# image_reject.net
KiCad netlist of a schematic drawn in Altium Designer
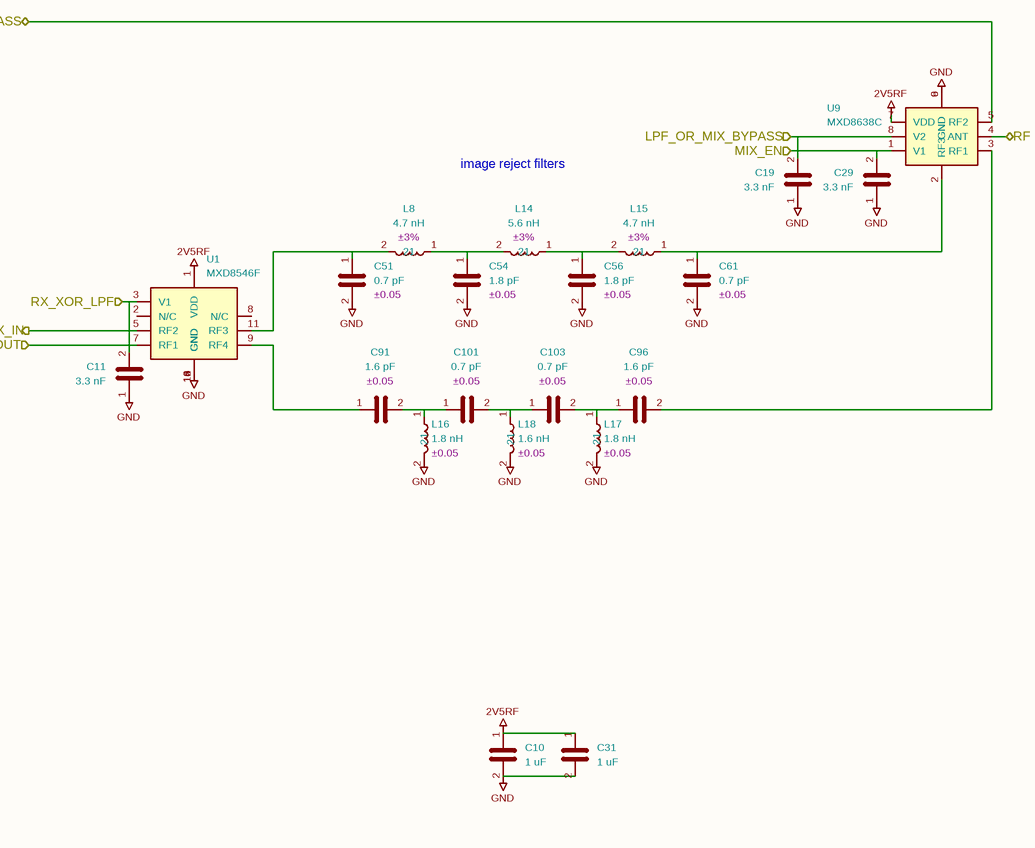
[diagram p0: image_reject.SchDoc]

(export (version "E")
  (design (tool "Eeschema 10.0.6"))
  (components
    (comp (ref "C10")
      (value "1 uF")
      (footprint "C_0201_0603Metric")
      (description "CAP CER 1UF 10V X5R 0201")
      (fields (field (name "MANUFACTURER") "Murata") (field (name "PART NUMBER") "GRM033R61A105ME44D"))
      (libsource (lib "Device") (part "C"))
    )
    (comp (ref "C11")
      (value "3.3 nF")
      (footprint "C_0201_0603Metric")
      (description "CAP CER 3300PF 10V X7R 0201")
      (fields (field (name "MANUFACTURER") "Murata") (field (name "PART NUMBER") "GRM033R71A332KA01D"))
      (libsource (lib "Device") (part "C"))
    )
    (comp (ref "C19")
      (value "3.3 nF")
      (footprint "C_0201_0603Metric")
      (description "CAP CER 3300PF 10V X7R 0201")
      (fields (field (name "MANUFACTURER") "Murata") (field (name "PART NUMBER") "GRM033R71A332KA01D"))
      (libsource (lib "Device") (part "C"))
    )
    (comp (ref "C29")
      (value "3.3 nF")
      (footprint "C_0201_0603Metric")
      (description "CAP CER 3300PF 10V X7R 0201")
      (fields (field (name "MANUFACTURER") "Murata") (field (name "PART NUMBER") "GRM033R71A332KA01D"))
      (libsource (lib "Device") (part "C"))
    )
    (comp (ref "C31")
      (value "1 uF")
      (footprint "C_0201_0603Metric")
      (description "CAP CER 1UF 10V X5R 0201")
      (fields (field (name "MANUFACTURER") "Murata") (field (name "PART NUMBER") "GRM033R61A105ME44D"))
      (libsource (lib "Device") (part "C"))
    )
    (comp (ref "C51")
      (value "0.7 pF")
      (footprint "C_0201_0603Metric")
      (description "CAP CER 0.7PF 25V C0G/NP0 0201")
      (fields
        (field (name "MANUFACTURER") "Murata")
        (field (name "PART NUMBER") "GRM0335C1ER70WA01D")
        (field (name "TOLERANCE") "±0.05")
      )
      (libsource (lib "Device") (part "C"))
    )
    (comp (ref "C54")
      (value "1.8 pF")
      (footprint "C_0201_0603Metric")
      (description "CAP CER 1.8PF 25V C0G/NP0 0201")
      (fields
        (field (name "MANUFACTURER") "Murata")
        (field (name "PART NUMBER") "GRM0335C1E1R8WA01D")
        (field (name "TOLERANCE") "±0.05")
      )
      (libsource (lib "Device") (part "C"))
    )
    (comp (ref "C56")
      (value "1.8 pF")
      (footprint "C_0201_0603Metric")
      (description "CAP CER 1.8PF 25V C0G/NP0 0201")
      (fields
        (field (name "MANUFACTURER") "Murata")
        (field (name "PART NUMBER") "GRM0335C1E1R8WA01D")
        (field (name "TOLERANCE") "±0.05")
      )
      (libsource (lib "Device") (part "C"))
    )
    (comp (ref "C61")
      (value "0.7 pF")
      (footprint "C_0201_0603Metric")
      (description "CAP CER 0.7PF 25V C0G/NP0 0201")
      (fields
        (field (name "MANUFACTURER") "Murata")
        (field (name "PART NUMBER") "GRM0335C1ER70WA01D")
        (field (name "TOLERANCE") "±0.05")
      )
      (libsource (lib "Device") (part "C"))
    )
    (comp (ref "C91")
      (value "1.6 pF")
      (footprint "C_0201_0603Metric")
      (description "CAP CER 1.6PF 25V C0G/NP0 0201")
      (fields
        (field (name "MANUFACTURER") "Murata")
        (field (name "PART NUMBER") "GRM0335C1E1R6WA01D")
        (field (name "TOLERANCE") "±0.05")
      )
      (libsource (lib "Device") (part "C"))
    )
    (comp (ref "C96")
      (value "1.6 pF")
      (footprint "C_0201_0603Metric")
      (description "CAP CER 1.6PF 25V C0G/NP0 0201")
      (fields
        (field (name "MANUFACTURER") "Murata")
        (field (name "PART NUMBER") "GRM0335C1E1R6WA01D")
        (field (name "TOLERANCE") "±0.05")
      )
      (libsource (lib "Device") (part "C"))
    )
    (comp (ref "C101")
      (value "0.7 pF")
      (footprint "C_0201_0603Metric")
      (description "CAP CER 0.7PF 25V C0G/NP0 0201")
      (fields
        (field (name "MANUFACTURER") "Murata")
        (field (name "PART NUMBER") "GRM0335C1ER70WA01D")
        (field (name "TOLERANCE") "±0.05")
      )
      (libsource (lib "Device") (part "C"))
    )
    (comp (ref "C103")
      (value "0.7 pF")
      (footprint "C_0201_0603Metric")
      (description "CAP CER 0.7PF 25V C0G/NP0 0201")
      (fields
        (field (name "MANUFACTURER") "Murata")
        (field (name "PART NUMBER") "GRM0335C1ER70WA01D")
        (field (name "TOLERANCE") "±0.05")
      )
      (libsource (lib "Device") (part "C"))
    )
    (comp (ref "L8")
      (value "4.7 nH")
      (footprint "L_0201_0603Metric")
      (description "FIXED IND 4.7NH 350MA 400MOHM 0201")
      (fields
        (field (name "MANUFACTURER") "Murata")
        (field (name "PART NUMBER") "LQP03TN4N7H02D")
        (field (name "TOLERANCE") "±3%")
      )
      (libsource (lib "Device") (part "L"))
    )
    (comp (ref "L14")
      (value "5.6 nH")
      (footprint "L_0201_0603Metric")
      (description "FIXED IND 5.6NH 350MA 400MOHM 0201")
      (fields
        (field (name "MANUFACTURER") "Murata")
        (field (name "PART NUMBER") "LQP03TN5N6H02D")
        (field (name "TOLERANCE") "±3%")
      )
      (libsource (lib "Device") (part "L"))
    )
    (comp (ref "L15")
      (value "4.7 nH")
      (footprint "L_0201_0603Metric")
      (description "FIXED IND 4.7NH 350MA 400MOHM 0201")
      (fields
        (field (name "MANUFACTURER") "Murata")
        (field (name "PART NUMBER") "LQP03TN4N7H02D")
        (field (name "TOLERANCE") "±3%")
      )
      (libsource (lib "Device") (part "L"))
    )
    (comp (ref "L16")
      (value "1.8 nH")
      (footprint "L_0201_0603Metric")
      (description "FIXED IND 1.8NH 800MA 0201 0.05")
      (fields
        (field (name "MANUFACTURER") "Murata")
        (field (name "PART NUMBER") "LQP03HQ1N8W02D")
        (field (name "TOLERANCE") "±0.05")
      )
      (libsource (lib "Device") (part "L"))
    )
    (comp (ref "L17")
      (value "1.8 nH")
      (footprint "L_0201_0603Metric")
      (description "FIXED IND 1.8NH 800MA 0201 0.05")
      (fields
        (field (name "MANUFACTURER") "Murata")
        (field (name "PART NUMBER") "LQP03HQ1N8W02D")
        (field (name "TOLERANCE") "±0.05")
      )
      (libsource (lib "Device") (part "L"))
    )
    (comp (ref "L18")
      (value "1.6 nH")
      (footprint "L_0201_0603Metric")
      (description "FIXED IND 1.6NH 1000MA 0201 0.05")
      (fields
        (field (name "MANUFACTURER") "Murata")
        (field (name "PART NUMBER") "LQP03HQ1N6W02D")
        (field (name "TOLERANCE") "±0.05")
      )
      (libsource (lib "Device") (part "L"))
    )
    (comp (ref "U1")
      (value "MXD8546F")
      (footprint "QFN-12-1EP_2x2mm_P0.5mm_EP1x1mm")
      (description "X-DPDT RF SWITCH")
      (fields (field (name "MANUFACTURER") "Maxscend"))
      (libsource (lib "praline") (part "MXD8546F"))
    )
    (comp (ref "U9")
      (value "MXD8638C")
      (footprint "MXD8638C")
      (description "Wideband RF SP3T Switch")
      (fields (field (name "MANUFACTURER") "Maxscend"))
      (libsource (lib "praline") (part "MXD8638"))
    )
  )
  (nets
    (net (code "1") (name "/LPF_OR_MIX_BYPASS") (class "Default")
      (node (ref "C19") (pin "2") (pinfunction "2_2") (pintype "passive"))
      (node (ref "U9") (pin "8") (pinfunction "V2_8") (pintype "passive"))
    )
    (net (code "2") (name "/MIX_BYPASS") (class "Default")
      (node (ref "U9") (pin "5") (pinfunction "RF2_5") (pintype "passive"))
    )
    (net (code "3") (name "/MIX_EN") (class "Default")
      (node (ref "C29") (pin "2") (pinfunction "2_2") (pintype "passive"))
      (node (ref "U9") (pin "1") (pinfunction "V1_1") (pintype "passive"))
    )
    (net (code "4") (name "/RF") (class "Default")
      (node (ref "U9") (pin "4") (pinfunction "ANT_4") (pintype "passive"))
    )
    (net (code "5") (name "/RX_MIX_IN") (class "Default")
      (node (ref "U1") (pin "5") (pinfunction "RF2_5") (pintype "passive"))
    )
    (net (code "6") (name "/RX_XOR_LPF") (class "Default")
      (node (ref "C11") (pin "2") (pinfunction "2_2") (pintype "passive"))
      (node (ref "U1") (pin "3") (pinfunction "V1_3") (pintype "passive"))
    )
    (net (code "7") (name "/TX_MIX_OUT") (class "Default")
      (node (ref "U1") (pin "7") (pinfunction "RF1_7") (pintype "passive"))
    )
    (net (code "8") (name "2V5RF") (class "Default")
      (node (ref "C10") (pin "1") (pinfunction "1_1") (pintype "passive"))
      (node (ref "C31") (pin "1") (pinfunction "1_1") (pintype "passive"))
      (node (ref "U1") (pin "1") (pinfunction "VDD_1") (pintype "passive"))
      (node (ref "U9") (pin "7") (pinfunction "VDD_7") (pintype "passive"))
    )
    (net (code "9") (name "GND") (class "Default")
      (node (ref "C10") (pin "2") (pinfunction "2_2") (pintype "passive"))
      (node (ref "C11") (pin "1") (pinfunction "1_1") (pintype "passive"))
      (node (ref "C19") (pin "1") (pinfunction "1_1") (pintype "passive"))
      (node (ref "C29") (pin "1") (pinfunction "1_1") (pintype "passive"))
      (node (ref "C31") (pin "2") (pinfunction "2_2") (pintype "passive"))
      (node (ref "C51") (pin "2") (pinfunction "2_2") (pintype "passive"))
      (node (ref "C54") (pin "2") (pinfunction "2_2") (pintype "passive"))
      (node (ref "C56") (pin "2") (pinfunction "2_2") (pintype "passive"))
      (node (ref "C61") (pin "2") (pinfunction "2_2") (pintype "passive"))
      (node (ref "L16") (pin "2") (pinfunction "2_2") (pintype "passive"))
      (node (ref "L17") (pin "2") (pinfunction "2_2") (pintype "passive"))
      (node (ref "L18") (pin "2") (pinfunction "2_2") (pintype "passive"))
      (node (ref "U1") (pin "10") (pinfunction "GND_10") (pintype "passive"))
      (node (ref "U1") (pin "12") (pinfunction "GND_12") (pintype "passive"))
      (node (ref "U1") (pin "13") (pinfunction "GND_13") (pintype "passive"))
      (node (ref "U1") (pin "4") (pinfunction "GND_4") (pintype "passive"))
      (node (ref "U1") (pin "6") (pinfunction "GND_6") (pintype "passive"))
      (node (ref "U9") (pin "6") (pinfunction "GND_6") (pintype "passive"))
      (node (ref "U9") (pin "9") (pinfunction "GND_9") (pintype "passive"))
    )
    (net (code "10") (name "Net-(C54-Pad1)") (class "Default")
      (node (ref "C54") (pin "1") (pinfunction "1_1") (pintype "passive"))
      (node (ref "L14") (pin "2") (pinfunction "2_2") (pintype "passive"))
      (node (ref "L8") (pin "1") (pinfunction "1_1") (pintype "passive"))
    )
    (net (code "11") (name "Net-(C56-Pad1)") (class "Default")
      (node (ref "C56") (pin "1") (pinfunction "1_1") (pintype "passive"))
      (node (ref "L14") (pin "1") (pinfunction "1_1") (pintype "passive"))
      (node (ref "L15") (pin "2") (pinfunction "2_2") (pintype "passive"))
    )
    (net (code "12") (name "Net-(C101-Pad1)") (class "Default")
      (node (ref "C101") (pin "1") (pinfunction "1_1") (pintype "passive"))
      (node (ref "C91") (pin "2") (pinfunction "2_2") (pintype "passive"))
      (node (ref "L16") (pin "1") (pinfunction "1_1") (pintype "passive"))
    )
    (net (code "13") (name "Net-(C101-Pad2)") (class "Default")
      (node (ref "C101") (pin "2") (pinfunction "2_2") (pintype "passive"))
      (node (ref "C103") (pin "1") (pinfunction "1_1") (pintype "passive"))
      (node (ref "L18") (pin "1") (pinfunction "1_1") (pintype "passive"))
    )
    (net (code "14") (name "Net-(C103-Pad2)") (class "Default")
      (node (ref "C103") (pin "2") (pinfunction "2_2") (pintype "passive"))
      (node (ref "C96") (pin "1") (pinfunction "1_1") (pintype "passive"))
      (node (ref "L17") (pin "1") (pinfunction "1_1") (pintype "passive"))
    )
    (net (code "15") (name "Net-(U1-RF3)") (class "Default")
      (node (ref "C51") (pin "1") (pinfunction "1_1") (pintype "passive"))
      (node (ref "L8") (pin "2") (pinfunction "2_2") (pintype "passive"))
      (node (ref "U1") (pin "11") (pinfunction "RF3_11") (pintype "passive"))
    )
    (net (code "16") (name "Net-(U1-RF4)") (class "Default")
      (node (ref "C91") (pin "1") (pinfunction "1_1") (pintype "passive"))
      (node (ref "U1") (pin "9") (pinfunction "RF4_9") (pintype "passive"))
    )
    (net (code "17") (name "Net-(U9-RF1)") (class "Default")
      (node (ref "C96") (pin "2") (pinfunction "2_2") (pintype "passive"))
      (node (ref "U9") (pin "3") (pinfunction "RF1_3") (pintype "passive"))
    )
    (net (code "18") (name "Net-(U9-RF3)") (class "Default")
      (node (ref "C61") (pin "1") (pinfunction "1_1") (pintype "passive"))
      (node (ref "L15") (pin "1") (pinfunction "1_1") (pintype "passive"))
      (node (ref "U9") (pin "2") (pinfunction "RF3_2") (pintype "passive"))
    )
    (net (code "19") (name "unconnected-(U1-N{slash}C-Pad2)") (class "Default")
      (node (ref "U1") (pin "2") (pinfunction "N/C_2") (pintype "passive"))
    )
    (net (code "20") (name "unconnected-(U1-N{slash}C-Pad8)") (class "Default")
      (node (ref "U1") (pin "8") (pinfunction "N/C_8") (pintype "passive"))
    )
  )
)
